# EPS_Battery_Controller_RLCL.net
KiCad netlist of a schematic drawn in Altium Designer
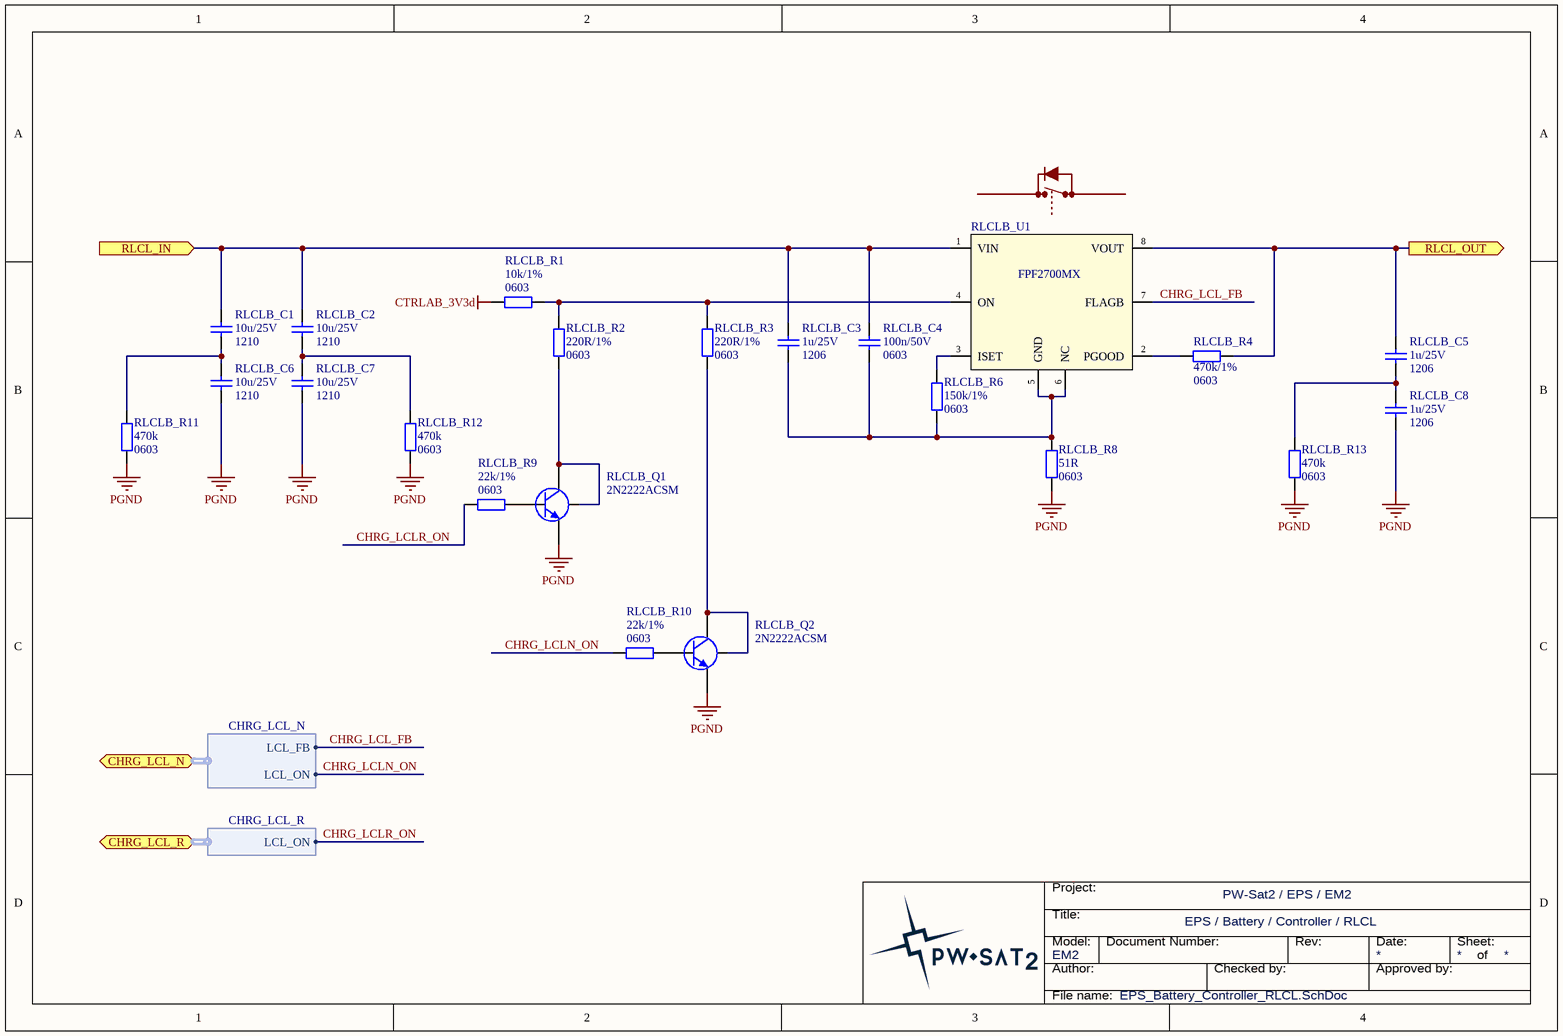
[diagram p0: EPS_Battery_Controller_RLCL.SchDoc]

(export (version "E")
  (design (tool "Eeschema 10.0.6"))
  (components
    (comp (ref "RLCLB_C1")
      (value "10u/25V")
      (footprint "SMD_Capacitor_1210")
      (description "Ceramic Cap Murata Automotive 10u/25V X7R 1210")
      (fields
        (field (name "MANUFACTURER") "Murata")
        (field (name "MANUFACTURERPARTNUMBER") "GCJ32ER71E106KA12L")
        (field (name "PACKAGE") "1210")
      )
      (libsource (lib "capacitors") (part "Cer_GCJ32ER71E106KA12L"))
    )
    (comp (ref "RLCLB_C2")
      (value "10u/25V")
      (footprint "SMD_Capacitor_1210")
      (description "Ceramic Cap Murata Automotive 10u/25V X7R 1210")
      (fields
        (field (name "MANUFACTURER") "Murata")
        (field (name "MANUFACTURERPARTNUMBER") "GCJ32ER71E106KA12L")
        (field (name "PACKAGE") "1210")
      )
      (libsource (lib "capacitors") (part "Cer_GCJ32ER71E106KA12L"))
    )
    (comp (ref "RLCLB_C3")
      (value "1u/25V")
      (footprint "SMD_Capacitor_1206")
      (description "Ceramic Cap Kemet COTS 1u/25V X7R 1206")
      (fields
        (field (name "MANUFACTURERPARTNUMBER") "C1206T105K3RALTU")
        (field (name "MANUFACTURER") "Kemet")
        (field (name "PACKAGE") "1206")
      )
      (libsource (lib "capacitors") (part "Cer_C1206T105K3RALTU"))
    )
    (comp (ref "RLCLB_C4")
      (value "100n/50V")
      (footprint "SMD_Capacitor_0603")
      (description "Ceramic Cap Murata Automotive 100n/50V X7R 0603")
      (fields
        (field (name "MANUFACTURER") "Murata")
        (field (name "MANUFACTURERPARTNUMBER") "GCJ188R71H104KA12D")
        (field (name "PACKAGE") "0603")
      )
      (libsource (lib "capacitors") (part "Cer_GCJ188R71H104KA12D"))
    )
    (comp (ref "RLCLB_C5")
      (value "1u/25V")
      (footprint "SMD_Capacitor_1206")
      (description "Ceramic Cap Kemet COTS 1u/25V X7R 1206")
      (fields
        (field (name "MANUFACTURERPARTNUMBER") "C1206T105K3RALTU")
        (field (name "MANUFACTURER") "Kemet")
        (field (name "PACKAGE") "1206")
      )
      (libsource (lib "capacitors") (part "Cer_C1206T105K3RALTU"))
    )
    (comp (ref "RLCLB_C6")
      (value "10u/25V")
      (footprint "SMD_Capacitor_1210")
      (description "Ceramic Cap Murata Automotive 10u/25V X7R 1210")
      (fields
        (field (name "MANUFACTURER") "Murata")
        (field (name "MANUFACTURERPARTNUMBER") "GCJ32ER71E106KA12L")
        (field (name "PACKAGE") "1210")
      )
      (libsource (lib "capacitors") (part "Cer_GCJ32ER71E106KA12L"))
    )
    (comp (ref "RLCLB_C7")
      (value "10u/25V")
      (footprint "SMD_Capacitor_1210")
      (description "Ceramic Cap Murata Automotive 10u/25V X7R 1210")
      (fields
        (field (name "MANUFACTURER") "Murata")
        (field (name "MANUFACTURERPARTNUMBER") "GCJ32ER71E106KA12L")
        (field (name "PACKAGE") "1210")
      )
      (libsource (lib "capacitors") (part "Cer_GCJ32ER71E106KA12L"))
    )
    (comp (ref "RLCLB_C8")
      (value "1u/25V")
      (footprint "SMD_Capacitor_1206")
      (description "Ceramic Cap Kemet COTS 1u/25V X7R 1206")
      (fields
        (field (name "MANUFACTURERPARTNUMBER") "C1206T105K3RALTU")
        (field (name "MANUFACTURER") "Kemet")
        (field (name "PACKAGE") "1206")
      )
      (libsource (lib "capacitors") (part "Cer_C1206T105K3RALTU"))
    )
    (comp (ref "RLCLB_Q1")
      (value "2N2222ACSM")
      (footprint "LCC1-4_BEC")
      (description "Silicon Planar Epitaxial NPN Transistor.")
      (fields (field (name "MANUFACTURER") "Semelab-TT"))
      (libsource (lib "transistors") (part "2N2222ACSM"))
    )
    (comp (ref "RLCLB_Q2")
      (value "2N2222ACSM")
      (footprint "LCC1-4_BEC")
      (description "Silicon Planar Epitaxial NPN Transistor.")
      (fields (field (name "MANUFACTURER") "Semelab-TT"))
      (libsource (lib "transistors") (part "2N2222ACSM"))
    )
    (comp (ref "RLCLB_R1")
      (value "10k/1%")
      (footprint "SMD_Resistor_0603")
      (fields (field (name "PACKAGE") "0603"))
      (libsource (lib "") (part "Res_1"))
    )
    (comp (ref "RLCLB_R2")
      (value "220R/1%")
      (footprint "SMD_Resistor_0603")
      (fields (field (name "PACKAGE") "0603"))
      (libsource (lib "") (part "Res_1"))
    )
    (comp (ref "RLCLB_R3")
      (value "220R/1%")
      (footprint "SMD_Resistor_0603")
      (fields (field (name "PACKAGE") "0603"))
      (libsource (lib "") (part "Res_1"))
    )
    (comp (ref "RLCLB_R4")
      (value "470k/1%")
      (footprint "SMD_Resistor_0603")
      (fields (field (name "PACKAGE") "0603"))
      (libsource (lib "") (part "Res_2"))
    )
    (comp (ref "RLCLB_R6")
      (value "150k/1%")
      (footprint "SMD_Resistor_0603")
      (fields (field (name "PACKAGE") "0603"))
      (libsource (lib "") (part "Res_1"))
    )
    (comp (ref "RLCLB_R8")
      (value "51R")
      (footprint "SMD_Resistor_0603")
      (fields (field (name "PACKAGE") "0603"))
      (libsource (lib "") (part "Res_1"))
    )
    (comp (ref "RLCLB_R9")
      (value "22k/1%")
      (footprint "SMD_Resistor_0603")
      (fields (field (name "PACKAGE") "0603"))
      (libsource (lib "resistors") (part "Res"))
    )
    (comp (ref "RLCLB_R10")
      (value "22k/1%")
      (footprint "SMD_Resistor_0603")
      (fields (field (name "PACKAGE") "0603"))
      (libsource (lib "resistors") (part "Res"))
    )
    (comp (ref "RLCLB_R11")
      (value "470k")
      (footprint "SMD_Resistor_0603")
      (fields (field (name "PACKAGE") "0603"))
      (libsource (lib "") (part "Res_1"))
    )
    (comp (ref "RLCLB_R12")
      (value "470k")
      (footprint "SMD_Resistor_0603")
      (fields (field (name "PACKAGE") "0603"))
      (libsource (lib "") (part "Res_1"))
    )
    (comp (ref "RLCLB_R13")
      (value "470k")
      (footprint "SMD_Resistor_0603")
      (fields (field (name "PACKAGE") "0603"))
      (libsource (lib "") (part "Res_1"))
    )
    (comp (ref "RLCLB_U1")
      (value "FPF2700MX")
      (footprint "SOIC-8-N")
      (description "Adj over-current protection 0.4-2A, Load Switch")
      (fields (field (name "MANUFACTURER") "Fairchild Semiconductor"))
      (libsource (lib "microcircuits") (part "FPF2700MX"))
    )
  )
  (nets
    (net (code "3") (name "/CHRG_LCLN_ON") (class "Default")
      (node (ref "RLCLB_R10") (pin "1") (pinfunction "1_1") (pintype "passive"))
    )
    (net (code "4") (name "/CHRG_LCLR_ON") (class "Default")
      (node (ref "RLCLB_R9") (pin "1") (pinfunction "1_1") (pintype "passive"))
    )
    (net (code "5") (name "/CHRG_LCL_FB") (class "Default")
      (node (ref "RLCLB_U1") (pin "7") (pinfunction "FLAGB_7") (pintype "passive"))
    )
    (net (code "6") (name "/RLCL_IN") (class "Default")
      (node (ref "RLCLB_C1") (pin "1") (pinfunction "1_1") (pintype "passive"))
      (node (ref "RLCLB_C2") (pin "1") (pinfunction "1_1") (pintype "passive"))
      (node (ref "RLCLB_C3") (pin "1") (pinfunction "1_1") (pintype "passive"))
      (node (ref "RLCLB_C4") (pin "1") (pinfunction "1_1") (pintype "passive"))
      (node (ref "RLCLB_U1") (pin "1") (pinfunction "VIN_1") (pintype "passive"))
    )
    (net (code "7") (name "/RLCL_OUT") (class "Default")
      (node (ref "RLCLB_C5") (pin "1") (pinfunction "1_1") (pintype "passive"))
      (node (ref "RLCLB_R4") (pin "2") (pinfunction "2_2") (pintype "passive"))
      (node (ref "RLCLB_U1") (pin "8") (pinfunction "VOUT_8") (pintype "passive"))
    )
    (net (code "10") (name "CTRLAB_3V3d") (class "Default")
      (node (ref "RLCLB_R1") (pin "2") (pinfunction "2_2") (pintype "passive"))
    )
    (net (code "11") (name "Net-(RLCLB_C1-Pad2)") (class "Default")
      (node (ref "RLCLB_C1") (pin "2") (pinfunction "2_2") (pintype "passive"))
      (node (ref "RLCLB_C6") (pin "1") (pinfunction "1_1") (pintype "passive"))
      (node (ref "RLCLB_R11") (pin "1") (pinfunction "1_1") (pintype "passive"))
    )
    (net (code "12") (name "Net-(RLCLB_C2-Pad2)") (class "Default")
      (node (ref "RLCLB_C2") (pin "2") (pinfunction "2_2") (pintype "passive"))
      (node (ref "RLCLB_C7") (pin "1") (pinfunction "1_1") (pintype "passive"))
      (node (ref "RLCLB_R12") (pin "1") (pinfunction "1_1") (pintype "passive"))
    )
    (net (code "13") (name "Net-(RLCLB_C5-Pad2)") (class "Default")
      (node (ref "RLCLB_C5") (pin "2") (pinfunction "2_2") (pintype "passive"))
      (node (ref "RLCLB_C8") (pin "1") (pinfunction "1_1") (pintype "passive"))
      (node (ref "RLCLB_R13") (pin "1") (pinfunction "1_1") (pintype "passive"))
    )
    (net (code "14") (name "Net-(RLCLB_Q1-PadB)") (class "Default")
      (node (ref "RLCLB_Q1") (pin "B") (pinfunction "B_B") (pintype "passive"))
      (node (ref "RLCLB_R9") (pin "2") (pinfunction "2_2") (pintype "passive"))
    )
    (net (code "15") (name "Net-(RLCLB_Q1-PadC)") (class "Default")
      (node (ref "RLCLB_Q1") (pin "C") (pinfunction "C_C") (pintype "passive"))
      (node (ref "RLCLB_Q1") (pin "Shield") (pinfunction "Shield_Shield") (pintype "passive"))
      (node (ref "RLCLB_R2") (pin "2") (pinfunction "2_2") (pintype "passive"))
    )
    (net (code "16") (name "Net-(RLCLB_Q2-PadB)") (class "Default")
      (node (ref "RLCLB_Q2") (pin "B") (pinfunction "B_B") (pintype "passive"))
      (node (ref "RLCLB_R10") (pin "2") (pinfunction "2_2") (pintype "passive"))
    )
    (net (code "17") (name "Net-(RLCLB_Q2-PadC)") (class "Default")
      (node (ref "RLCLB_Q2") (pin "C") (pinfunction "C_C") (pintype "passive"))
      (node (ref "RLCLB_Q2") (pin "Shield") (pinfunction "Shield_Shield") (pintype "passive"))
      (node (ref "RLCLB_R3") (pin "2") (pinfunction "2_2") (pintype "passive"))
    )
    (net (code "18") (name "Net-(RLCLB_U1-GND)") (class "Default")
      (node (ref "RLCLB_C3") (pin "2") (pinfunction "2_2") (pintype "passive"))
      (node (ref "RLCLB_C4") (pin "2") (pinfunction "2_2") (pintype "passive"))
      (node (ref "RLCLB_R6") (pin "2") (pinfunction "2_2") (pintype "passive"))
      (node (ref "RLCLB_R8") (pin "1") (pinfunction "1_1") (pintype "passive"))
      (node (ref "RLCLB_U1") (pin "5") (pinfunction "GND_5") (pintype "passive"))
      (node (ref "RLCLB_U1") (pin "6") (pinfunction "NC_6") (pintype "passive"))
    )
    (net (code "19") (name "Net-(RLCLB_U1-ISET)") (class "Default")
      (node (ref "RLCLB_R6") (pin "1") (pinfunction "1_1") (pintype "passive"))
      (node (ref "RLCLB_U1") (pin "3") (pinfunction "ISET_3") (pintype "passive"))
    )
    (net (code "20") (name "Net-(RLCLB_U1-ON)") (class "Default")
      (node (ref "RLCLB_R1") (pin "1") (pinfunction "1_1") (pintype "passive"))
      (node (ref "RLCLB_R2") (pin "1") (pinfunction "1_1") (pintype "passive"))
      (node (ref "RLCLB_R3") (pin "1") (pinfunction "1_1") (pintype "passive"))
      (node (ref "RLCLB_U1") (pin "4") (pinfunction "ON_4") (pintype "passive"))
    )
    (net (code "21") (name "Net-(RLCLB_U1-PGOOD)") (class "Default")
      (node (ref "RLCLB_R4") (pin "1") (pinfunction "1_1") (pintype "passive"))
      (node (ref "RLCLB_U1") (pin "2") (pinfunction "PGOOD_2") (pintype "passive"))
    )
    (net (code "22") (name "PGND") (class "Default")
      (node (ref "RLCLB_C6") (pin "2") (pinfunction "2_2") (pintype "passive"))
      (node (ref "RLCLB_C7") (pin "2") (pinfunction "2_2") (pintype "passive"))
      (node (ref "RLCLB_C8") (pin "2") (pinfunction "2_2") (pintype "passive"))
      (node (ref "RLCLB_Q1") (pin "E") (pinfunction "E_E") (pintype "passive"))
      (node (ref "RLCLB_Q2") (pin "E") (pinfunction "E_E") (pintype "passive"))
      (node (ref "RLCLB_R11") (pin "2") (pinfunction "2_2") (pintype "passive"))
      (node (ref "RLCLB_R12") (pin "2") (pinfunction "2_2") (pintype "passive"))
      (node (ref "RLCLB_R13") (pin "2") (pinfunction "2_2") (pintype "passive"))
      (node (ref "RLCLB_R8") (pin "2") (pinfunction "2_2") (pintype "passive"))
    )
  )
)
